# 13-UWB-Antenna.net
KiCad netlist of a schematic drawn in Altium Designer
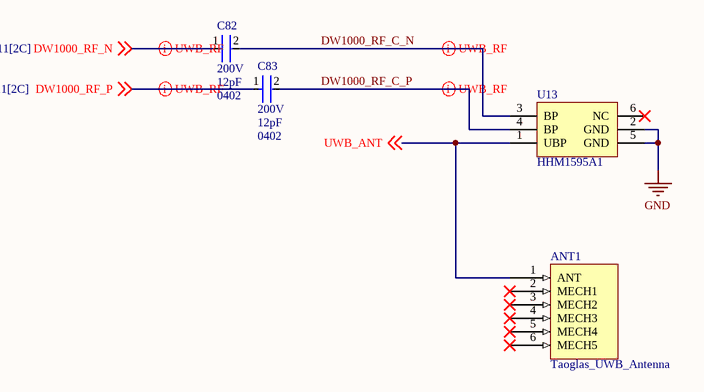
[diagram p0: 13-UWB-Antenna.SchDoc]

(export (version "E")
  (design (tool "Eeschema 10.0.6"))
  (components
    (comp (ref "ANT1")
      (value "Taoglas_UWB_Antenna")
      (footprint "UWC.20 Antenna")
      (libsource (lib "TimeDrive_Lib") (part "Taoglas_UWB_Antenna"))
    )
    (comp (ref "C82")
      (value "GQM1555C2D120FB01D")
      (footprint "FP-GQM155-0_05-MFG")
      (description "Ceramic Capacitor 12pF  ±1% 200VDC C0G 0402 Paper T/R")
      (fields
        (field (name "VOLTAGE RATING (DC)") "200V")
        (field (name "TOLERANCE") "1%")
        (field (name "CAPACITANCE") "12pF")
        (field (name "CASE/PACKAGE") "0402")
      )
      (libsource (lib "Altium Content Vault") (part "11868f565c42a9108669ba33697ecf6"))
    )
    (comp (ref "C83")
      (value "GQM1555C2D120FB01D")
      (footprint "FP-GQM155-0_05-MFG")
      (description "Ceramic Capacitor 12pF  ±1% 200VDC C0G 0402 Paper T/R")
      (fields
        (field (name "VOLTAGE RATING (DC)") "200V")
        (field (name "TOLERANCE") "1%")
        (field (name "CAPACITANCE") "12pF")
        (field (name "CASE/PACKAGE") "0402")
      )
      (libsource (lib "Altium Content Vault") (part "11868f565c42a9108669ba33697ecf6"))
    )
    (comp (ref "U13")
      (value "HHM1595A1")
      (footprint "TDK-HHM1595A1_V")
      (description "Multilayer Balun, 3000 to 8000 MHz, -40 to 85 degC, 6-Pin SMD, RoHS, Tape and Reel")
      (fields (field (name "MANUFACTURER") "TDK"))
      (libsource (lib "Altium Content Vault") (part "TDK-HHM1595A1-6"))
    )
  )
  (nets
    (net (code "1") (name "/DW1000_RF_C_N") (class "Default")
      (node (ref "C82") (pin "2") (pinfunction "2_2") (pintype "passive"))
      (node (ref "U13") (pin "3") (pinfunction "BP_3") (pintype "passive"))
    )
    (net (code "2") (name "/DW1000_RF_C_P") (class "Default")
      (node (ref "C83") (pin "2") (pinfunction "2_2") (pintype "passive"))
      (node (ref "U13") (pin "4") (pinfunction "BP_4") (pintype "passive"))
    )
    (net (code "3") (name "DW1000_RF_N") (class "Default")
      (node (ref "C82") (pin "1") (pinfunction "1_1") (pintype "passive"))
    )
    (net (code "4") (name "DW1000_RF_P") (class "Default")
      (node (ref "C83") (pin "1") (pinfunction "1_1") (pintype "passive"))
    )
    (net (code "5") (name "GND") (class "Default")
      (node (ref "U13") (pin "2") (pinfunction "GND_2") (pintype "power_in"))
      (node (ref "U13") (pin "5") (pinfunction "GND_5") (pintype "power_in"))
    )
    (net (code "6") (name "UWB_ANT") (class "Default")
      (node (ref "ANT1") (pin "1") (pinfunction "ANT_1") (pintype "input"))
      (node (ref "U13") (pin "1") (pinfunction "UBP_1") (pintype "passive"))
    )
    (net (code "7") (name "unconnected-(ANT1-MECH1-Pad2)") (class "Default")
      (node (ref "ANT1") (pin "2") (pinfunction "MECH1_2") (pintype "input+no_connect"))
    )
    (net (code "8") (name "unconnected-(ANT1-MECH2-Pad3)") (class "Default")
      (node (ref "ANT1") (pin "3") (pinfunction "MECH2_3") (pintype "input+no_connect"))
    )
    (net (code "9") (name "unconnected-(ANT1-MECH3-Pad4)") (class "Default")
      (node (ref "ANT1") (pin "4") (pinfunction "MECH3_4") (pintype "input+no_connect"))
    )
    (net (code "10") (name "unconnected-(ANT1-MECH4-Pad5)") (class "Default")
      (node (ref "ANT1") (pin "5") (pinfunction "MECH4_5") (pintype "input+no_connect"))
    )
    (net (code "11") (name "unconnected-(ANT1-MECH5-Pad6)") (class "Default")
      (node (ref "ANT1") (pin "6") (pinfunction "MECH5_6") (pintype "input+no_connect"))
    )
    (net (code "12") (name "unconnected-(U13-NC-Pad6)") (class "Default")
      (node (ref "U13") (pin "6") (pinfunction "NC_6") (pintype "passive+no_connect"))
    )
  )
)
